# PFETswitch.net
KiCad netlist of a schematic drawn in EAGLE
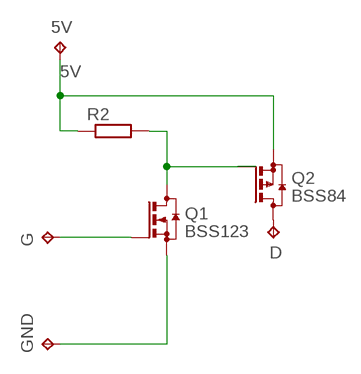
[diagram p0: schematic, sheet 1]

(export (version "E")
  (design (tool "Eeschema 10.0.6"))
  (components
    (comp (ref "5V")
      (value "TPTP09SQ")
      (footprint "eagle-import:TP09SQ")
      (libsource (lib "eagle-import") (part "TPTP09SQ"))
    )
    (comp (ref "D")
      (value "TPTP09SQ")
      (footprint "eagle-import:TP09SQ")
      (libsource (lib "eagle-import") (part "TPTP09SQ"))
    )
    (comp (ref "G")
      (value "TPTP09SQ")
      (footprint "eagle-import:TP09SQ")
      (libsource (lib "eagle-import") (part "TPTP09SQ"))
    )
    (comp (ref "GND")
      (value "TPTP09SQ")
      (footprint "eagle-import:TP09SQ")
      (libsource (lib "eagle-import") (part "TPTP09SQ"))
    )
    (comp (ref "Q1")
      (value "BSS123")
      (footprint "eagle-import:SOT23")
      (libsource (lib "eagle-import") (part "BSS123"))
    )
    (comp (ref "Q2")
      (value "BSS84")
      (footprint "eagle-import:SOT23")
      (libsource (lib "eagle-import") (part "BSS84"))
    )
    (comp (ref "R2")
      (value "R-EU_R0603")
      (footprint "eagle-import:R0603")
      (libsource (lib "eagle-import") (part "R-EU_R0603"))
    )
  )
  (nets
    (net (code "1") (name "/5V") (class "Default")
      (node (ref "5V") (pin "TP") (pinfunction "TP_TP") (pintype "input"))
      (node (ref "Q2") (pin "2") (pinfunction "S_2") (pintype "passive"))
      (node (ref "R2") (pin "1") (pinfunction "1_1") (pintype "passive"))
    )
    (net (code "2") (name "Net-(Q1-D)") (class "Default")
      (node (ref "Q1") (pin "3") (pinfunction "D_3") (pintype "passive"))
      (node (ref "Q2") (pin "1") (pinfunction "G_1") (pintype "passive"))
      (node (ref "R2") (pin "2") (pinfunction "2_2") (pintype "passive"))
    )
    (net (code "3") (name "Net-(Q1-G)") (class "Default")
      (node (ref "G") (pin "TP") (pinfunction "TP_TP") (pintype "input"))
      (node (ref "Q1") (pin "1") (pinfunction "G_1") (pintype "passive"))
    )
    (net (code "4") (name "Net-(Q1-S)") (class "Default")
      (node (ref "GND") (pin "TP") (pinfunction "TP_TP") (pintype "input"))
      (node (ref "Q1") (pin "2") (pinfunction "S_2") (pintype "passive"))
    )
    (net (code "5") (name "Net-(Q2-D)") (class "Default")
      (node (ref "D") (pin "TP") (pinfunction "TP_TP") (pintype "input"))
      (node (ref "Q2") (pin "3") (pinfunction "D_3") (pintype "passive"))
    )
  )
)
